# sche.net
KiCad netlist of a schematic drawn in Altium Designer
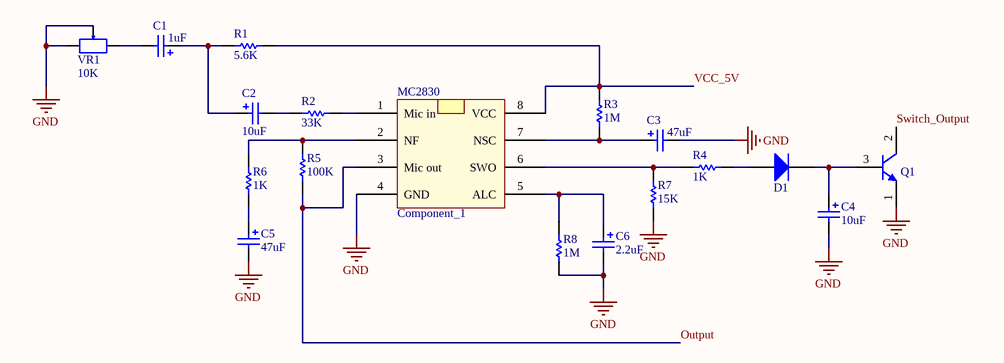
[diagram p0: sche.SchDoc]

(export (version "E")
  (design (tool "Eeschema 10.0.6"))
  (components
    (comp (ref "C1")
      (value "1uF")
      (footprint "CP1/2")
      (description "Polarized Capacitor (Radial)")
      (fields (field (name "Comment") "Cap Pol"))
      (libsource (lib "PIF_Library") (part "Cap Pol"))
    )
    (comp (ref "C2")
      (value "10uF")
      (footprint "CP1/2")
      (description "Polarized Capacitor (Radial)")
      (fields (field (name "Comment") "Cap Pol"))
      (libsource (lib "PIF_Library") (part "Cap Pol"))
    )
    (comp (ref "C3")
      (value "47uF")
      (footprint "CP1/2.5")
      (description "Polarized Capacitor (Radial)")
      (fields (field (name "Comment") "Cap Pol"))
      (libsource (lib "PIF_Library") (part "Cap Pol"))
    )
    (comp (ref "C4")
      (value "10uF")
      (footprint "CP1/2")
      (description "Polarized Capacitor (Radial)")
      (fields (field (name "Comment") "Cap Pol"))
      (libsource (lib "PIF_Library") (part "Cap Pol"))
    )
    (comp (ref "C5")
      (value "47uF")
      (footprint "CP1/2.5")
      (description "Polarized Capacitor (Radial)")
      (fields (field (name "Comment") "Cap Pol"))
      (libsource (lib "PIF_Library") (part "Cap Pol"))
    )
    (comp (ref "C6")
      (value "2.2uF")
      (footprint "CP1/2")
      (description "Polarized Capacitor (Radial)")
      (fields (field (name "Comment") "Cap Pol"))
      (libsource (lib "PIF_Library") (part "Cap Pol"))
    )
    (comp (ref "D1")
      (value "Diode")
      (footprint "D1A")
      (description "Default Diode")
      (libsource (lib "PIF_Library") (part "Diode"))
    )
    (comp (ref "MC2830")
      (value "Component_1")
      (footprint "DIP8")
      (libsource (lib "Sche") (part "Component_1"))
    )
    (comp (ref "Q1")
      (value "C1815")
      (footprint "QTO-92")
      (description "NPN Bipolar Transistor")
      (libsource (lib "PIF_Library") (part "C1815"))
    )
    (comp (ref "R1")
      (value "5.6K")
      (footprint "RES 1/2W")
      (description "Resistor")
      (fields (field (name "Comment") "RESISTOR"))
      (libsource (lib "PIF_Library") (part "RESISTOR"))
    )
    (comp (ref "R2")
      (value "33K")
      (footprint "RES 1/2W")
      (description "Resistor")
      (fields (field (name "Comment") "RESISTOR"))
      (libsource (lib "PIF_Library") (part "RESISTOR"))
    )
    (comp (ref "R3")
      (value "1M")
      (footprint "RES 1/2W")
      (description "Resistor")
      (fields (field (name "Comment") "RESISTOR"))
      (libsource (lib "PIF_Library") (part "RESISTOR"))
    )
    (comp (ref "R4")
      (value "1K")
      (footprint "RES 1/2W")
      (description "Resistor")
      (fields (field (name "Comment") "RESISTOR"))
      (libsource (lib "PIF_Library") (part "RESISTOR"))
    )
    (comp (ref "R5")
      (value "100K")
      (footprint "RES 1/2W")
      (description "Resistor")
      (fields (field (name "Comment") "RESISTOR"))
      (libsource (lib "PIF_Library") (part "RESISTOR"))
    )
    (comp (ref "R6")
      (value "1K")
      (footprint "RES 1/2W")
      (description "Resistor")
      (fields (field (name "Comment") "RESISTOR"))
      (libsource (lib "PIF_Library") (part "RESISTOR"))
    )
    (comp (ref "R7")
      (value "15K")
      (footprint "RES 1/2W")
      (description "Resistor")
      (fields (field (name "Comment") "RESISTOR"))
      (libsource (lib "PIF_Library") (part "RESISTOR"))
    )
    (comp (ref "R8")
      (value "1M")
      (footprint "RES 1/2W")
      (description "Resistor")
      (fields (field (name "Comment") "RESISTOR"))
      (libsource (lib "PIF_Library") (part "RESISTOR"))
    )
    (comp (ref "VR1")
      (value "10K")
      (footprint "VR")
      (description "Var Resistor")
      (libsource (lib "syhaunguyen") (part "VR"))
    )
  )
  (nets
    (net (code "1") (name "/Output") (class "Default")
      (node (ref "MC2830") (pin "3") (pinfunction "Mic_out_3") (pintype "passive"))
      (node (ref "R5") (pin "1") (pinfunction "1_1") (pintype "passive"))
    )
    (net (code "2") (name "/Switch_Output") (class "Default")
      (node (ref "Q1") (pin "2") (pinfunction "C_2") (pintype "passive"))
    )
    (net (code "3") (name "/VCC_5V") (class "Default")
      (node (ref "MC2830") (pin "8") (pinfunction "VCC_8") (pintype "passive"))
      (node (ref "R1") (pin "2") (pinfunction "2_2") (pintype "passive"))
      (node (ref "R3") (pin "2") (pinfunction "2_2") (pintype "passive"))
    )
    (net (code "4") (name "GND") (class "Default")
      (node (ref "C3") (pin "2") (pinfunction "2_2") (pintype "passive"))
      (node (ref "C4") (pin "2") (pinfunction "2_2") (pintype "passive"))
      (node (ref "C5") (pin "2") (pinfunction "2_2") (pintype "passive"))
      (node (ref "C6") (pin "2") (pinfunction "2_2") (pintype "passive"))
      (node (ref "MC2830") (pin "4") (pinfunction "GND_4") (pintype "passive"))
      (node (ref "Q1") (pin "1") (pinfunction "E_1") (pintype "passive"))
      (node (ref "R7") (pin "1") (pinfunction "1_1") (pintype "passive"))
      (node (ref "R8") (pin "1") (pinfunction "1_1") (pintype "passive"))
      (node (ref "VR1") (pin "1") (pinfunction "1_1") (pintype "passive"))
      (node (ref "VR1") (pin "2") (pinfunction "2_2") (pintype "passive"))
    )
    (net (code "5") (name "Net-(C1-Pad1)") (class "Default")
      (node (ref "C1") (pin "1") (pinfunction "1_1") (pintype "passive"))
      (node (ref "C2") (pin "1") (pinfunction "1_1") (pintype "passive"))
      (node (ref "R1") (pin "1") (pinfunction "1_1") (pintype "passive"))
    )
    (net (code "6") (name "Net-(C1-Pad2)") (class "Default")
      (node (ref "C1") (pin "2") (pinfunction "2_2") (pintype "passive"))
      (node (ref "VR1") (pin "3") (pinfunction "3_3") (pintype "passive"))
    )
    (net (code "7") (name "Net-(C2-Pad2)") (class "Default")
      (node (ref "C2") (pin "2") (pinfunction "2_2") (pintype "passive"))
      (node (ref "R2") (pin "1") (pinfunction "1_1") (pintype "passive"))
    )
    (net (code "8") (name "Net-(C5-Pad1)") (class "Default")
      (node (ref "C5") (pin "1") (pinfunction "1_1") (pintype "passive"))
      (node (ref "R6") (pin "1") (pinfunction "1_1") (pintype "passive"))
    )
    (net (code "9") (name "Net-(D1-A)") (class "Default")
      (node (ref "D1") (pin "1") (pinfunction "A_1") (pintype "passive"))
      (node (ref "R4") (pin "2") (pinfunction "2_2") (pintype "passive"))
    )
    (net (code "10") (name "Net-(D1-K)") (class "Default")
      (node (ref "C4") (pin "1") (pinfunction "1_1") (pintype "passive"))
      (node (ref "D1") (pin "2") (pinfunction "K_2") (pintype "passive"))
      (node (ref "Q1") (pin "3") (pinfunction "B_3") (pintype "passive"))
    )
    (net (code "11") (name "Net-(MC2830-ALC)") (class "Default")
      (node (ref "C6") (pin "1") (pinfunction "1_1") (pintype "passive"))
      (node (ref "MC2830") (pin "5") (pinfunction "ALC_5") (pintype "passive"))
      (node (ref "R8") (pin "2") (pinfunction "2_2") (pintype "passive"))
    )
    (net (code "12") (name "Net-(MC2830-Mic_in)") (class "Default")
      (node (ref "MC2830") (pin "1") (pinfunction "Mic_in_1") (pintype "passive"))
      (node (ref "R2") (pin "2") (pinfunction "2_2") (pintype "passive"))
    )
    (net (code "13") (name "Net-(MC2830-NF)") (class "Default")
      (node (ref "MC2830") (pin "2") (pinfunction "NF_2") (pintype "passive"))
      (node (ref "R5") (pin "2") (pinfunction "2_2") (pintype "passive"))
      (node (ref "R6") (pin "2") (pinfunction "2_2") (pintype "passive"))
    )
    (net (code "14") (name "Net-(MC2830-NSC)") (class "Default")
      (node (ref "C3") (pin "1") (pinfunction "1_1") (pintype "passive"))
      (node (ref "MC2830") (pin "7") (pinfunction "NSC_7") (pintype "passive"))
      (node (ref "R3") (pin "1") (pinfunction "1_1") (pintype "passive"))
    )
    (net (code "15") (name "Net-(MC2830-SWO)") (class "Default")
      (node (ref "MC2830") (pin "6") (pinfunction "SWO_6") (pintype "passive"))
      (node (ref "R4") (pin "1") (pinfunction "1_1") (pintype "passive"))
      (node (ref "R7") (pin "2") (pinfunction "2_2") (pintype "passive"))
    )
  )
)
